# Passive_Filter_PCB_Design_Large_Board.net
KiCad netlist of a schematic drawn in EAGLE
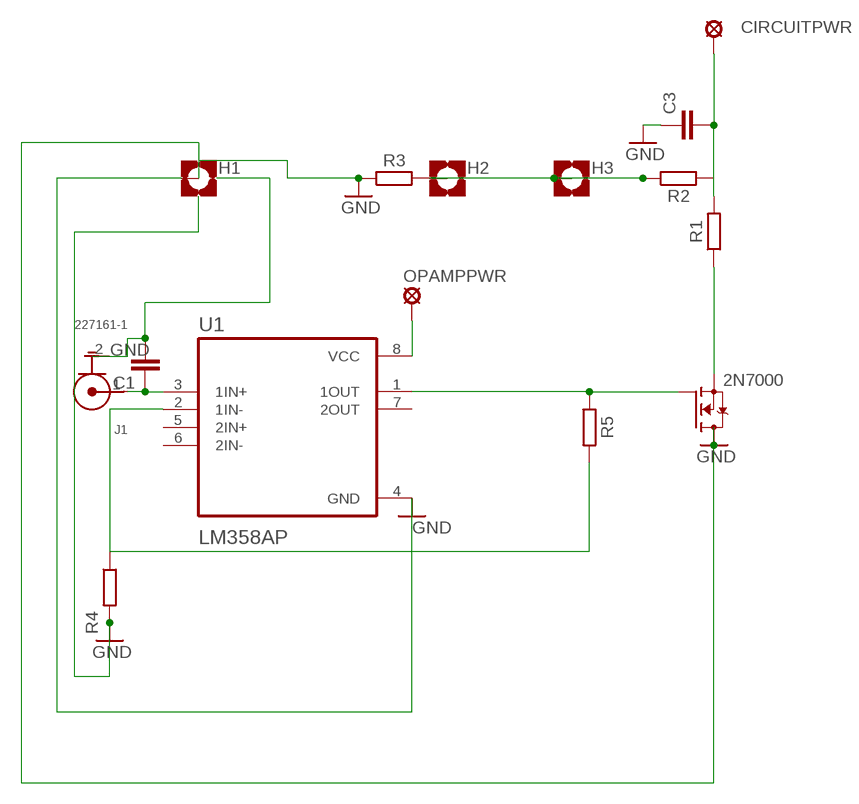
[diagram p0: schematic, sheet 1]

(export (version "E")
  (design (tool "Eeschema 10.0.6"))
  (components
    (comp (ref "C1")
      (value "C5/3.5")
      (footprint "eagle-import:C5B3.5")
      (libsource (lib "eagle-import") (part "C5/3.5"))
    )
    (comp (ref "C3")
      (value "C5/3.5")
      (footprint "eagle-import:C5B3.5")
      (libsource (lib "eagle-import") (part "C5/3.5"))
    )
    (comp (ref "CIRCUITPWR")
      (value "MCS10B")
      (footprint "eagle-import:MCS10B")
      (libsource (lib "eagle-import") (part "MCS10B"))
    )
    (comp (ref "H1")
      (value "MOUNT-PAD-SQUARE2.8")
      (footprint "eagle-import:2,8-PAD-SQUARE")
      (libsource (lib "eagle-import") (part "MOUNT-PAD-SQUARE2.8"))
    )
    (comp (ref "H2")
      (value "MOUNT-PAD-SQUARE2.8")
      (footprint "eagle-import:2,8-PAD-SQUARE")
      (libsource (lib "eagle-import") (part "MOUNT-PAD-SQUARE2.8"))
    )
    (comp (ref "H3")
      (value "MOUNT-PAD-SQUARE2.8")
      (footprint "eagle-import:2,8-PAD-SQUARE")
      (libsource (lib "eagle-import") (part "MOUNT-PAD-SQUARE2.8"))
    )
    (comp (ref "J1")
      (value "227161-1")
      (footprint "eagle-import:TE_227161-1")
      (fields (field (name "MF") "TE Connectivity"))
      (libsource (lib "eagle-import") (part "227161-1"))
    )
    (comp (ref "OPAMPPWR")
      (value "LSP10")
      (footprint "eagle-import:LSP10")
      (libsource (lib "eagle-import") (part "LSP10"))
    )
    (comp (ref "R1")
      (value "R_AXIAL-7.2MM-PITCH")
      (footprint "eagle-import:RESAD724W46L381D178B")
      (libsource (lib "eagle-import") (part "RAXIAL-7.2MM-PITCH_"))
    )
    (comp (ref "R2")
      (value "R_AXIAL-7.2MM-PITCH")
      (footprint "eagle-import:RESAD724W46L381D178B")
      (libsource (lib "eagle-import") (part "RAXIAL-7.2MM-PITCH_"))
    )
    (comp (ref "R3")
      (value "R_AXIAL-7.2MM-PITCH")
      (footprint "eagle-import:RESAD724W46L381D178B")
      (libsource (lib "eagle-import") (part "RAXIAL-7.2MM-PITCH_"))
    )
    (comp (ref "R4")
      (value "R_AXIAL-7.2MM-PITCH")
      (footprint "eagle-import:RESAD724W46L381D178B")
      (libsource (lib "eagle-import") (part "RAXIAL-7.2MM-PITCH_"))
    )
    (comp (ref "R5")
      (value "R_AXIAL-7.2MM-PITCH")
      (footprint "eagle-import:RESAD724W46L381D178B")
      (libsource (lib "eagle-import") (part "RAXIAL-7.2MM-PITCH_"))
    )
    (comp (ref "SHUNT")
      (value "2N7000")
      (footprint "eagle-import:TO92-")
      (fields (field (name "MF") "STMicroelectronics"))
      (libsource (lib "eagle-import") (part "2N7000"))
    )
    (comp (ref "U1")
      (value "LM358AP")
      (footprint "eagle-import:DIP794W45P254L959H508Q8")
      (fields (field (name "MF") "Texas Instruments"))
      (libsource (lib "eagle-import") (part "LM358AP"))
    )
  )
  (nets
    (net (code "1") (name "GND") (class "Default")
      (node (ref "C1") (pin "2") (pinfunction "2_2") (pintype "passive"))
      (node (ref "C3") (pin "1") (pinfunction "1_1") (pintype "passive"))
      (node (ref "H1") (pin "B2,8") (pinfunction "MOUNT_B2,8") (pintype "passive"))
      (node (ref "J1") (pin "2") (pinfunction "G_2") (pintype "power_in"))
      (node (ref "R3") (pin "1") (pinfunction "1_1") (pintype "passive"))
      (node (ref "R4") (pin "2") (pinfunction "2_2") (pintype "passive"))
      (node (ref "SHUNT") (pin "1") (pinfunction "D_1") (pintype "passive"))
      (node (ref "U1") (pin "4") (pinfunction "GND_4") (pintype "power_in"))
    )
    (net (code "2") (name "Net-(C3-Pad2)") (class "Default")
      (node (ref "C3") (pin "2") (pinfunction "2_2") (pintype "passive"))
      (node (ref "CIRCUITPWR") (pin "MP") (pinfunction "MP_MP") (pintype "passive"))
      (node (ref "R1") (pin "2") (pinfunction "2_2") (pintype "passive"))
      (node (ref "R2") (pin "2") (pinfunction "2_2") (pintype "passive"))
    )
    (net (code "3") (name "Net-(H2-MOUNT)") (class "Default")
      (node (ref "H2") (pin "B2,8") (pinfunction "MOUNT_B2,8") (pintype "passive"))
      (node (ref "H3") (pin "B2,8") (pinfunction "MOUNT_B2,8") (pintype "passive"))
      (node (ref "R2") (pin "1") (pinfunction "1_1") (pintype "passive"))
      (node (ref "R3") (pin "2") (pinfunction "2_2") (pintype "passive"))
    )
    (net (code "4") (name "Net-(J1-C)") (class "Default")
      (node (ref "C1") (pin "1") (pinfunction "1_1") (pintype "passive"))
      (node (ref "J1") (pin "1") (pinfunction "C_1") (pintype "passive"))
      (node (ref "U1") (pin "3") (pinfunction "1IN+_3") (pintype "input"))
    )
    (net (code "5") (name "Net-(SHUNT-G)") (class "Default")
      (node (ref "R5") (pin "1") (pinfunction "1_1") (pintype "passive"))
      (node (ref "SHUNT") (pin "2") (pinfunction "G_2") (pintype "passive"))
      (node (ref "U1") (pin "1") (pinfunction "1OUT_1") (pintype "output"))
    )
    (net (code "6") (name "Net-(SHUNT-S)") (class "Default")
      (node (ref "R1") (pin "1") (pinfunction "1_1") (pintype "passive"))
      (node (ref "SHUNT") (pin "3") (pinfunction "S_3") (pintype "passive"))
    )
    (net (code "7") (name "Net-(U1-1IN-)") (class "Default")
      (node (ref "R4") (pin "1") (pinfunction "1_1") (pintype "passive"))
      (node (ref "R5") (pin "2") (pinfunction "2_2") (pintype "passive"))
      (node (ref "U1") (pin "2") (pinfunction "1IN-_2") (pintype "input"))
    )
    (net (code "8") (name "Net-(U1-VCC)") (class "Default")
      (node (ref "OPAMPPWR") (pin "MP") (pinfunction "MP_MP") (pintype "passive"))
      (node (ref "U1") (pin "8") (pinfunction "VCC_8") (pintype "power_in"))
    )
    (net (code "9") (name "unconnected-(U1-2IN+-Pad5)") (class "Default")
      (node (ref "U1") (pin "5") (pinfunction "2IN+_5") (pintype "input"))
    )
    (net (code "10") (name "unconnected-(U1-2IN--Pad6)") (class "Default")
      (node (ref "U1") (pin "6") (pinfunction "2IN-_6") (pintype "input"))
    )
    (net (code "11") (name "unconnected-(U1-2OUT-Pad7)") (class "Default")
      (node (ref "U1") (pin "7") (pinfunction "2OUT_7") (pintype "output"))
    )
  )
)
